# simpleROM.net
KiCad netlist of a schematic drawn in EAGLE
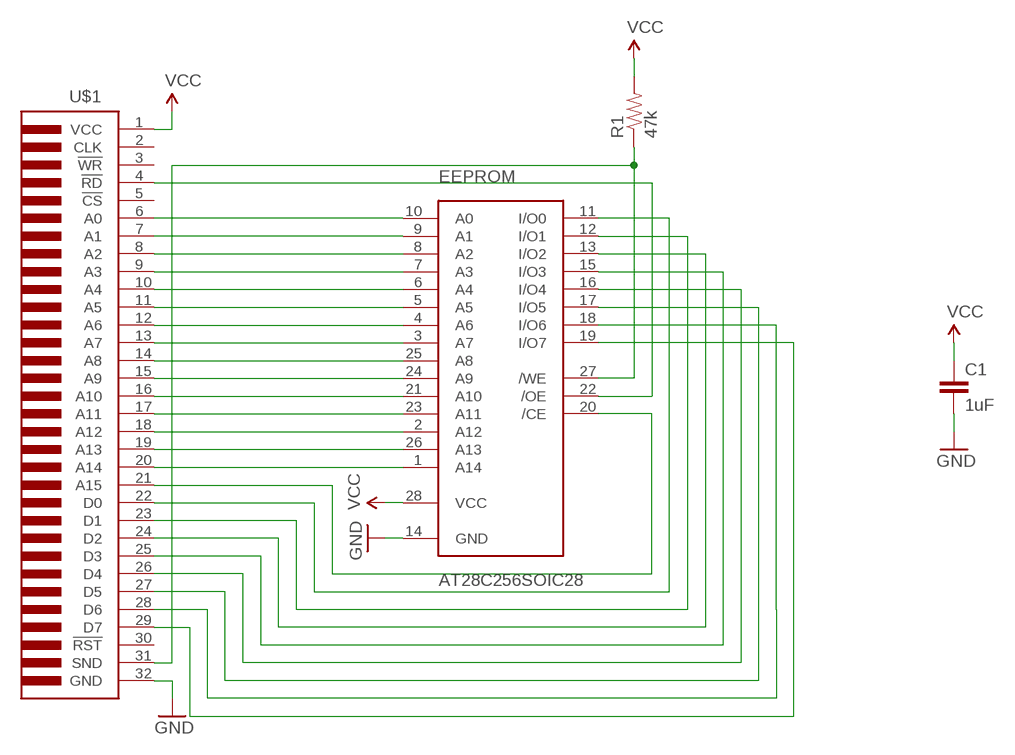
[diagram p0: schematic, sheet 1]

(export (version "E")
  (design (tool "Eeschema 10.0.6"))
  (components
    (comp (ref "C1")
      (value "1uF")
      (footprint "eagle-import:SPARKFUN-CAPACITORS_1206")
      (libsource (lib "eagle-import") (part "SPARKFUN-CAPACITORS_CAP1206"))
    )
    (comp (ref "EEPROM")
      (value "AT28C256SOIC28")
      (footprint "eagle-import:SO28")
      (libsource (lib "eagle-import") (part "AT28C256SOIC28"))
    )
    (comp (ref "R1")
      (value "47k")
      (footprint "eagle-import:SPARKFUN-RESISTORS_1206")
      (libsource (lib "eagle-import") (part "SPARKFUN-RESISTORS_RESISTOR1206"))
    )
    (comp (ref "U$1")
      (value "GBCART-FULL")
      (footprint "eagle-import:GBCART")
      (libsource (lib "eagle-import") (part "GBCART-FULL"))
    )
  )
  (nets
    (net (code "1") (name "GND") (class "Default")
      (node (ref "C1") (pin "2") (pinfunction "2_2") (pintype "passive"))
      (node (ref "EEPROM") (pin "14") (pinfunction "GND_14") (pintype "bidirectional"))
      (node (ref "U$1") (pin "32") (pinfunction "GND_32") (pintype "power_in"))
    )
    (net (code "2") (name "Net-(EEPROM-A0)") (class "Default")
      (node (ref "EEPROM") (pin "10") (pinfunction "A0_10") (pintype "bidirectional"))
      (node (ref "U$1") (pin "6") (pinfunction "A0_6") (pintype "output"))
    )
    (net (code "3") (name "Net-(EEPROM-A1)") (class "Default")
      (node (ref "EEPROM") (pin "9") (pinfunction "A1_9") (pintype "bidirectional"))
      (node (ref "U$1") (pin "7") (pinfunction "A1_7") (pintype "output"))
    )
    (net (code "4") (name "Net-(EEPROM-A2)") (class "Default")
      (node (ref "EEPROM") (pin "8") (pinfunction "A2_8") (pintype "bidirectional"))
      (node (ref "U$1") (pin "8") (pinfunction "A2_8") (pintype "output"))
    )
    (net (code "5") (name "Net-(EEPROM-A3)") (class "Default")
      (node (ref "EEPROM") (pin "7") (pinfunction "A3_7") (pintype "bidirectional"))
      (node (ref "U$1") (pin "9") (pinfunction "A3_9") (pintype "output"))
    )
    (net (code "6") (name "Net-(EEPROM-A4)") (class "Default")
      (node (ref "EEPROM") (pin "6") (pinfunction "A4_6") (pintype "bidirectional"))
      (node (ref "U$1") (pin "10") (pinfunction "A4_10") (pintype "output"))
    )
    (net (code "7") (name "Net-(EEPROM-A5)") (class "Default")
      (node (ref "EEPROM") (pin "5") (pinfunction "A5_5") (pintype "bidirectional"))
      (node (ref "U$1") (pin "11") (pinfunction "A5_11") (pintype "output"))
    )
    (net (code "8") (name "Net-(EEPROM-A6)") (class "Default")
      (node (ref "EEPROM") (pin "4") (pinfunction "A6_4") (pintype "bidirectional"))
      (node (ref "U$1") (pin "12") (pinfunction "A6_12") (pintype "output"))
    )
    (net (code "9") (name "Net-(EEPROM-A7)") (class "Default")
      (node (ref "EEPROM") (pin "3") (pinfunction "A7_3") (pintype "bidirectional"))
      (node (ref "U$1") (pin "13") (pinfunction "A7_13") (pintype "output"))
    )
    (net (code "10") (name "Net-(EEPROM-A8)") (class "Default")
      (node (ref "EEPROM") (pin "25") (pinfunction "A8_25") (pintype "bidirectional"))
      (node (ref "U$1") (pin "14") (pinfunction "A8_14") (pintype "output"))
    )
    (net (code "11") (name "Net-(EEPROM-A9)") (class "Default")
      (node (ref "EEPROM") (pin "24") (pinfunction "A9_24") (pintype "bidirectional"))
      (node (ref "U$1") (pin "15") (pinfunction "A9_15") (pintype "output"))
    )
    (net (code "12") (name "Net-(EEPROM-A10)") (class "Default")
      (node (ref "EEPROM") (pin "21") (pinfunction "A10_21") (pintype "bidirectional"))
      (node (ref "U$1") (pin "16") (pinfunction "A10_16") (pintype "output"))
    )
    (net (code "13") (name "Net-(EEPROM-A11)") (class "Default")
      (node (ref "EEPROM") (pin "23") (pinfunction "A11_23") (pintype "bidirectional"))
      (node (ref "U$1") (pin "17") (pinfunction "A11_17") (pintype "output"))
    )
    (net (code "14") (name "Net-(EEPROM-A12)") (class "Default")
      (node (ref "EEPROM") (pin "2") (pinfunction "A12_2") (pintype "bidirectional"))
      (node (ref "U$1") (pin "18") (pinfunction "A12_18") (pintype "output"))
    )
    (net (code "15") (name "Net-(EEPROM-A13)") (class "Default")
      (node (ref "EEPROM") (pin "26") (pinfunction "A13_26") (pintype "bidirectional"))
      (node (ref "U$1") (pin "19") (pinfunction "A13_19") (pintype "output"))
    )
    (net (code "16") (name "Net-(EEPROM-A14)") (class "Default")
      (node (ref "EEPROM") (pin "1") (pinfunction "A14_1") (pintype "bidirectional"))
      (node (ref "U$1") (pin "20") (pinfunction "A14_20") (pintype "output"))
    )
    (net (code "17") (name "Net-(EEPROM-I{slash}O0)") (class "Default")
      (node (ref "EEPROM") (pin "11") (pinfunction "I/O0_11") (pintype "bidirectional"))
      (node (ref "U$1") (pin "22") (pinfunction "D0_22") (pintype "bidirectional"))
    )
    (net (code "18") (name "Net-(EEPROM-I{slash}O1)") (class "Default")
      (node (ref "EEPROM") (pin "12") (pinfunction "I/O1_12") (pintype "bidirectional"))
      (node (ref "U$1") (pin "23") (pinfunction "D1_23") (pintype "bidirectional"))
    )
    (net (code "19") (name "Net-(EEPROM-I{slash}O2)") (class "Default")
      (node (ref "EEPROM") (pin "13") (pinfunction "I/O2_13") (pintype "bidirectional"))
      (node (ref "U$1") (pin "24") (pinfunction "D2_24") (pintype "bidirectional"))
    )
    (net (code "20") (name "Net-(EEPROM-I{slash}O3)") (class "Default")
      (node (ref "EEPROM") (pin "15") (pinfunction "I/O3_15") (pintype "bidirectional"))
      (node (ref "U$1") (pin "25") (pinfunction "D3_25") (pintype "bidirectional"))
    )
    (net (code "21") (name "Net-(EEPROM-I{slash}O4)") (class "Default")
      (node (ref "EEPROM") (pin "16") (pinfunction "I/O4_16") (pintype "bidirectional"))
      (node (ref "U$1") (pin "26") (pinfunction "D4_26") (pintype "bidirectional"))
    )
    (net (code "22") (name "Net-(EEPROM-I{slash}O5)") (class "Default")
      (node (ref "EEPROM") (pin "17") (pinfunction "I/O5_17") (pintype "bidirectional"))
      (node (ref "U$1") (pin "27") (pinfunction "D5_27") (pintype "bidirectional"))
    )
    (net (code "23") (name "Net-(EEPROM-I{slash}O6)") (class "Default")
      (node (ref "EEPROM") (pin "18") (pinfunction "I/O6_18") (pintype "bidirectional"))
      (node (ref "U$1") (pin "28") (pinfunction "D6_28") (pintype "bidirectional"))
    )
    (net (code "24") (name "Net-(EEPROM-I{slash}O7)") (class "Default")
      (node (ref "EEPROM") (pin "19") (pinfunction "I/O7_19") (pintype "bidirectional"))
      (node (ref "U$1") (pin "29") (pinfunction "D7_29") (pintype "bidirectional"))
    )
    (net (code "25") (name "Net-(EEPROM-{slash}CE)") (class "Default")
      (node (ref "EEPROM") (pin "20") (pinfunction "/CE_20") (pintype "bidirectional"))
      (node (ref "U$1") (pin "21") (pinfunction "A15_21") (pintype "output"))
    )
    (net (code "26") (name "Net-(EEPROM-{slash}OE)") (class "Default")
      (node (ref "EEPROM") (pin "22") (pinfunction "/OE_22") (pintype "bidirectional"))
      (node (ref "U$1") (pin "4") (pinfunction "~{RD}_4") (pintype "output"))
    )
    (net (code "27") (name "Net-(EEPROM-{slash}WE)") (class "Default")
      (node (ref "EEPROM") (pin "27") (pinfunction "/WE_27") (pintype "bidirectional"))
      (node (ref "R1") (pin "1") (pinfunction "1_1") (pintype "passive"))
      (node (ref "U$1") (pin "31") (pinfunction "SND_31") (pintype "bidirectional"))
    )
    (net (code "28") (name "VCC") (class "Default")
      (node (ref "C1") (pin "1") (pinfunction "1_1") (pintype "passive"))
      (node (ref "EEPROM") (pin "28") (pinfunction "VCC_28") (pintype "bidirectional"))
      (node (ref "R1") (pin "2") (pinfunction "2_2") (pintype "passive"))
      (node (ref "U$1") (pin "1") (pinfunction "VCC_1") (pintype "power_in"))
    )
    (net (code "29") (name "unconnected-(U$1-CLK-Pad2)") (class "Default")
      (node (ref "U$1") (pin "2") (pinfunction "CLK_2") (pintype "output"))
    )
    (net (code "30") (name "unconnected-(U$1-~{CS}-Pad5)") (class "Default")
      (node (ref "U$1") (pin "5") (pinfunction "~{CS}_5") (pintype "output"))
    )
    (net (code "31") (name "unconnected-(U$1-~{RST}-Pad30)") (class "Default")
      (node (ref "U$1") (pin "30") (pinfunction "~{RST}_30") (pintype "bidirectional"))
    )
    (net (code "32") (name "unconnected-(U$1-~{WR}-Pad3)") (class "Default")
      (node (ref "U$1") (pin "3") (pinfunction "~{WR}_3") (pintype "output"))
    )
  )
)
